# APP_1_JTAG_m.net
KiCad netlist of a schematic drawn in Altium Designer
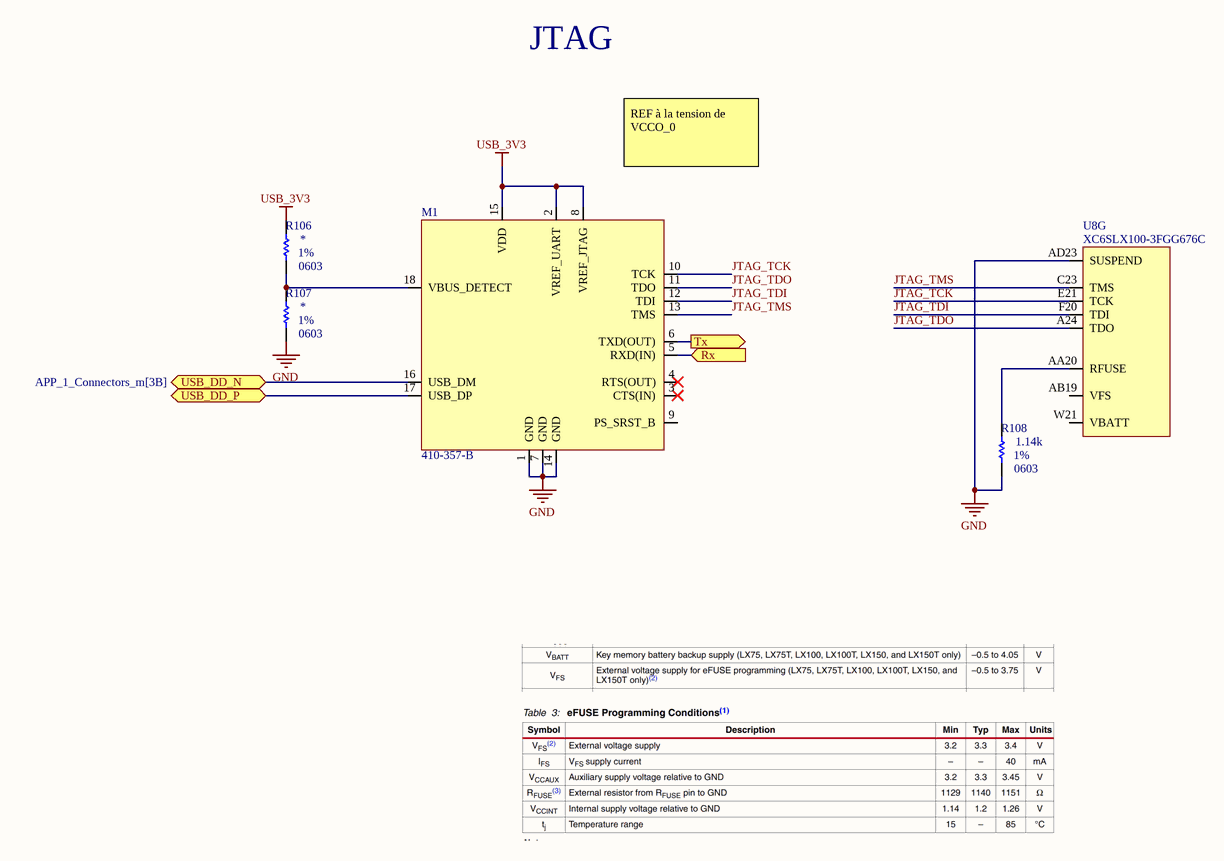
[diagram p0: APP_1_JTAG_m.SchDoc]

(export (version "E")
  (design (tool "Eeschema 10.0.6"))
  (components
    (comp (ref "M1")
      (value "410-357-B")
      (footprint "MOD_JTAG_410-357-B")
      (description "MOD - JTAG-SMT3-NC Programming Module For Xilinx FPGA - 18-SMT")
      (fields
        (field (name "CREATEDBY/DATE") "Tommy Rossignol 2018-11-23")
        (field (name "VERIFIEDBY") "Nicolas V. (2019-01-28)")
      )
      (libsource (lib "S7CAS_LIB2023") (part "MOD_JTAG_410-357-B"))
    )
    (comp (ref "R106")
      (value "RES - 0603")
      (footprint "RES_0603")
      (fields
        (field (name "PACKAGE") "0603")
        (field (name "PRECISION") "1%")
        (field (name "ALTIUM_VALUE") "*")
        (field (name "CREATEDBY") "Jonathan Bouchard")
      )
      (libsource (lib "S7CAS_LIB2023") (part "RES - 0603"))
    )
    (comp (ref "R107")
      (value "RES - 0603")
      (footprint "RES_0603")
      (fields
        (field (name "PACKAGE") "0603")
        (field (name "PRECISION") "1%")
        (field (name "ALTIUM_VALUE") "*")
        (field (name "CREATEDBY") "Jonathan Bouchard")
      )
      (libsource (lib "S7CAS_LIB2023") (part "RES - 0603"))
    )
    (comp (ref "R108")
      (value "1.14k")
      (footprint "RES_0603")
      (description "RES - 0603")
      (fields
        (field (name "PACKAGE") "0603")
        (field (name "PRECISION") "1%")
        (field (name "CREATEDBY") "Jonathan Bouchard")
      )
      (libsource (lib "S7CAS_LIB2023") (part "RES - 0603"))
    )
    (comp (ref "U8")
      (value "XC6SLX100-3FGG676C")
      (footprint "FPGA_XILINX_FGG676")
      (description "FPGA - XILINX SPARTAN 6 480 I/O - BGA-676")
      (fields
        (field (name "VOLTAGE") "1.14 V ~ 1.26 V")
        (field (name "MFG") "Xilinx")
        (field (name "CREATEDBY") "Jonathan Bouchard")
      )
      (libsource (lib "S7CAS_LIB2023") (part "FPGA_XC6SLX100-3FGG676C"))
    )
  )
  (nets
    (net (code "1") (name "/JTAG_TCK") (class "Default")
      (node (ref "M1") (pin "10") (pinfunction "TCK_10") (pintype "passive"))
      (node (ref "U8") (pin "E21") (pinfunction "TCK_E21") (pintype "passive"))
    )
    (net (code "2") (name "/JTAG_TDI") (class "Default")
      (node (ref "M1") (pin "12") (pinfunction "TDI_12") (pintype "passive"))
      (node (ref "U8") (pin "F20") (pinfunction "TDI_F20") (pintype "passive"))
    )
    (net (code "3") (name "/JTAG_TDO") (class "Default")
      (node (ref "M1") (pin "11") (pinfunction "TDO_11") (pintype "passive"))
      (node (ref "U8") (pin "A24") (pinfunction "TDO_A24") (pintype "passive"))
    )
    (net (code "4") (name "/JTAG_TMS") (class "Default")
      (node (ref "M1") (pin "13") (pinfunction "TMS_13") (pintype "passive"))
      (node (ref "U8") (pin "C23") (pinfunction "TMS_C23") (pintype "passive"))
    )
    (net (code "5") (name "/Rx") (class "Default")
      (node (ref "M1") (pin "5") (pinfunction "RXD(IN)_5") (pintype "passive"))
    )
    (net (code "6") (name "/Tx") (class "Default")
      (node (ref "M1") (pin "6") (pinfunction "TXD(OUT)_6") (pintype "passive"))
    )
    (net (code "7") (name "/USB_DD_N") (class "Default")
      (node (ref "M1") (pin "16") (pinfunction "USB_DM_16") (pintype "passive"))
    )
    (net (code "8") (name "/USB_DD_P") (class "Default")
      (node (ref "M1") (pin "17") (pinfunction "USB_DP_17") (pintype "passive"))
    )
    (net (code "9") (name "GND") (class "Default")
      (node (ref "M1") (pin "1") (pinfunction "GND_1") (pintype "passive"))
      (node (ref "M1") (pin "14") (pinfunction "GND_14") (pintype "passive"))
      (node (ref "M1") (pin "7") (pinfunction "GND_7") (pintype "passive"))
      (node (ref "R107") (pin "1") (pinfunction "1_1") (pintype "passive"))
      (node (ref "R108") (pin "1") (pinfunction "1_1") (pintype "passive"))
      (node (ref "U8") (pin "AD23") (pinfunction "SUSPEND_AD23") (pintype "passive"))
    )
    (net (code "10") (name "Net-(M1-VBUS_DETECT)") (class "Default")
      (node (ref "M1") (pin "18") (pinfunction "VBUS_DETECT_18") (pintype "passive"))
      (node (ref "R106") (pin "1") (pinfunction "1_1") (pintype "passive"))
      (node (ref "R107") (pin "2") (pinfunction "2_2") (pintype "passive"))
    )
    (net (code "11") (name "Net-(U8G-RFUSE)") (class "Default")
      (node (ref "R108") (pin "2") (pinfunction "2_2") (pintype "passive"))
      (node (ref "U8") (pin "AA20") (pinfunction "RFUSE_AA20") (pintype "passive"))
    )
    (net (code "12") (name "USB_3V3") (class "Default")
      (node (ref "M1") (pin "15") (pinfunction "VDD_15") (pintype "passive"))
      (node (ref "M1") (pin "2") (pinfunction "VREF_UART_2") (pintype "passive"))
      (node (ref "M1") (pin "8") (pinfunction "VREF_JTAG_8") (pintype "passive"))
      (node (ref "R106") (pin "2") (pinfunction "2_2") (pintype "passive"))
    )
    (net (code "13") (name "unconnected-(M1-CTS(IN)-Pad3)") (class "Default")
      (node (ref "M1") (pin "3") (pinfunction "CTS(IN)_3") (pintype "passive+no_connect"))
    )
    (net (code "14") (name "unconnected-(M1-PS_SRST_B-Pad9)") (class "Default")
      (node (ref "M1") (pin "9") (pinfunction "PS_SRST_B_9") (pintype "passive"))
    )
    (net (code "15") (name "unconnected-(M1-RTS(OUT)-Pad4)") (class "Default")
      (node (ref "M1") (pin "4") (pinfunction "RTS(OUT)_4") (pintype "passive+no_connect"))
    )
    (net (code "16") (name "unconnected-(U8G-VBATT-PadW21)") (class "Default")
      (node (ref "U8") (pin "W21") (pinfunction "VBATT_W21") (pintype "passive"))
    )
    (net (code "17") (name "unconnected-(U8G-VFS-PadAB19)") (class "Default")
      (node (ref "U8") (pin "AB19") (pinfunction "VFS_AB19") (pintype "passive"))
    )
  )
)
